# ADS1256.net
KiCad netlist of a schematic drawn in Altium Designer
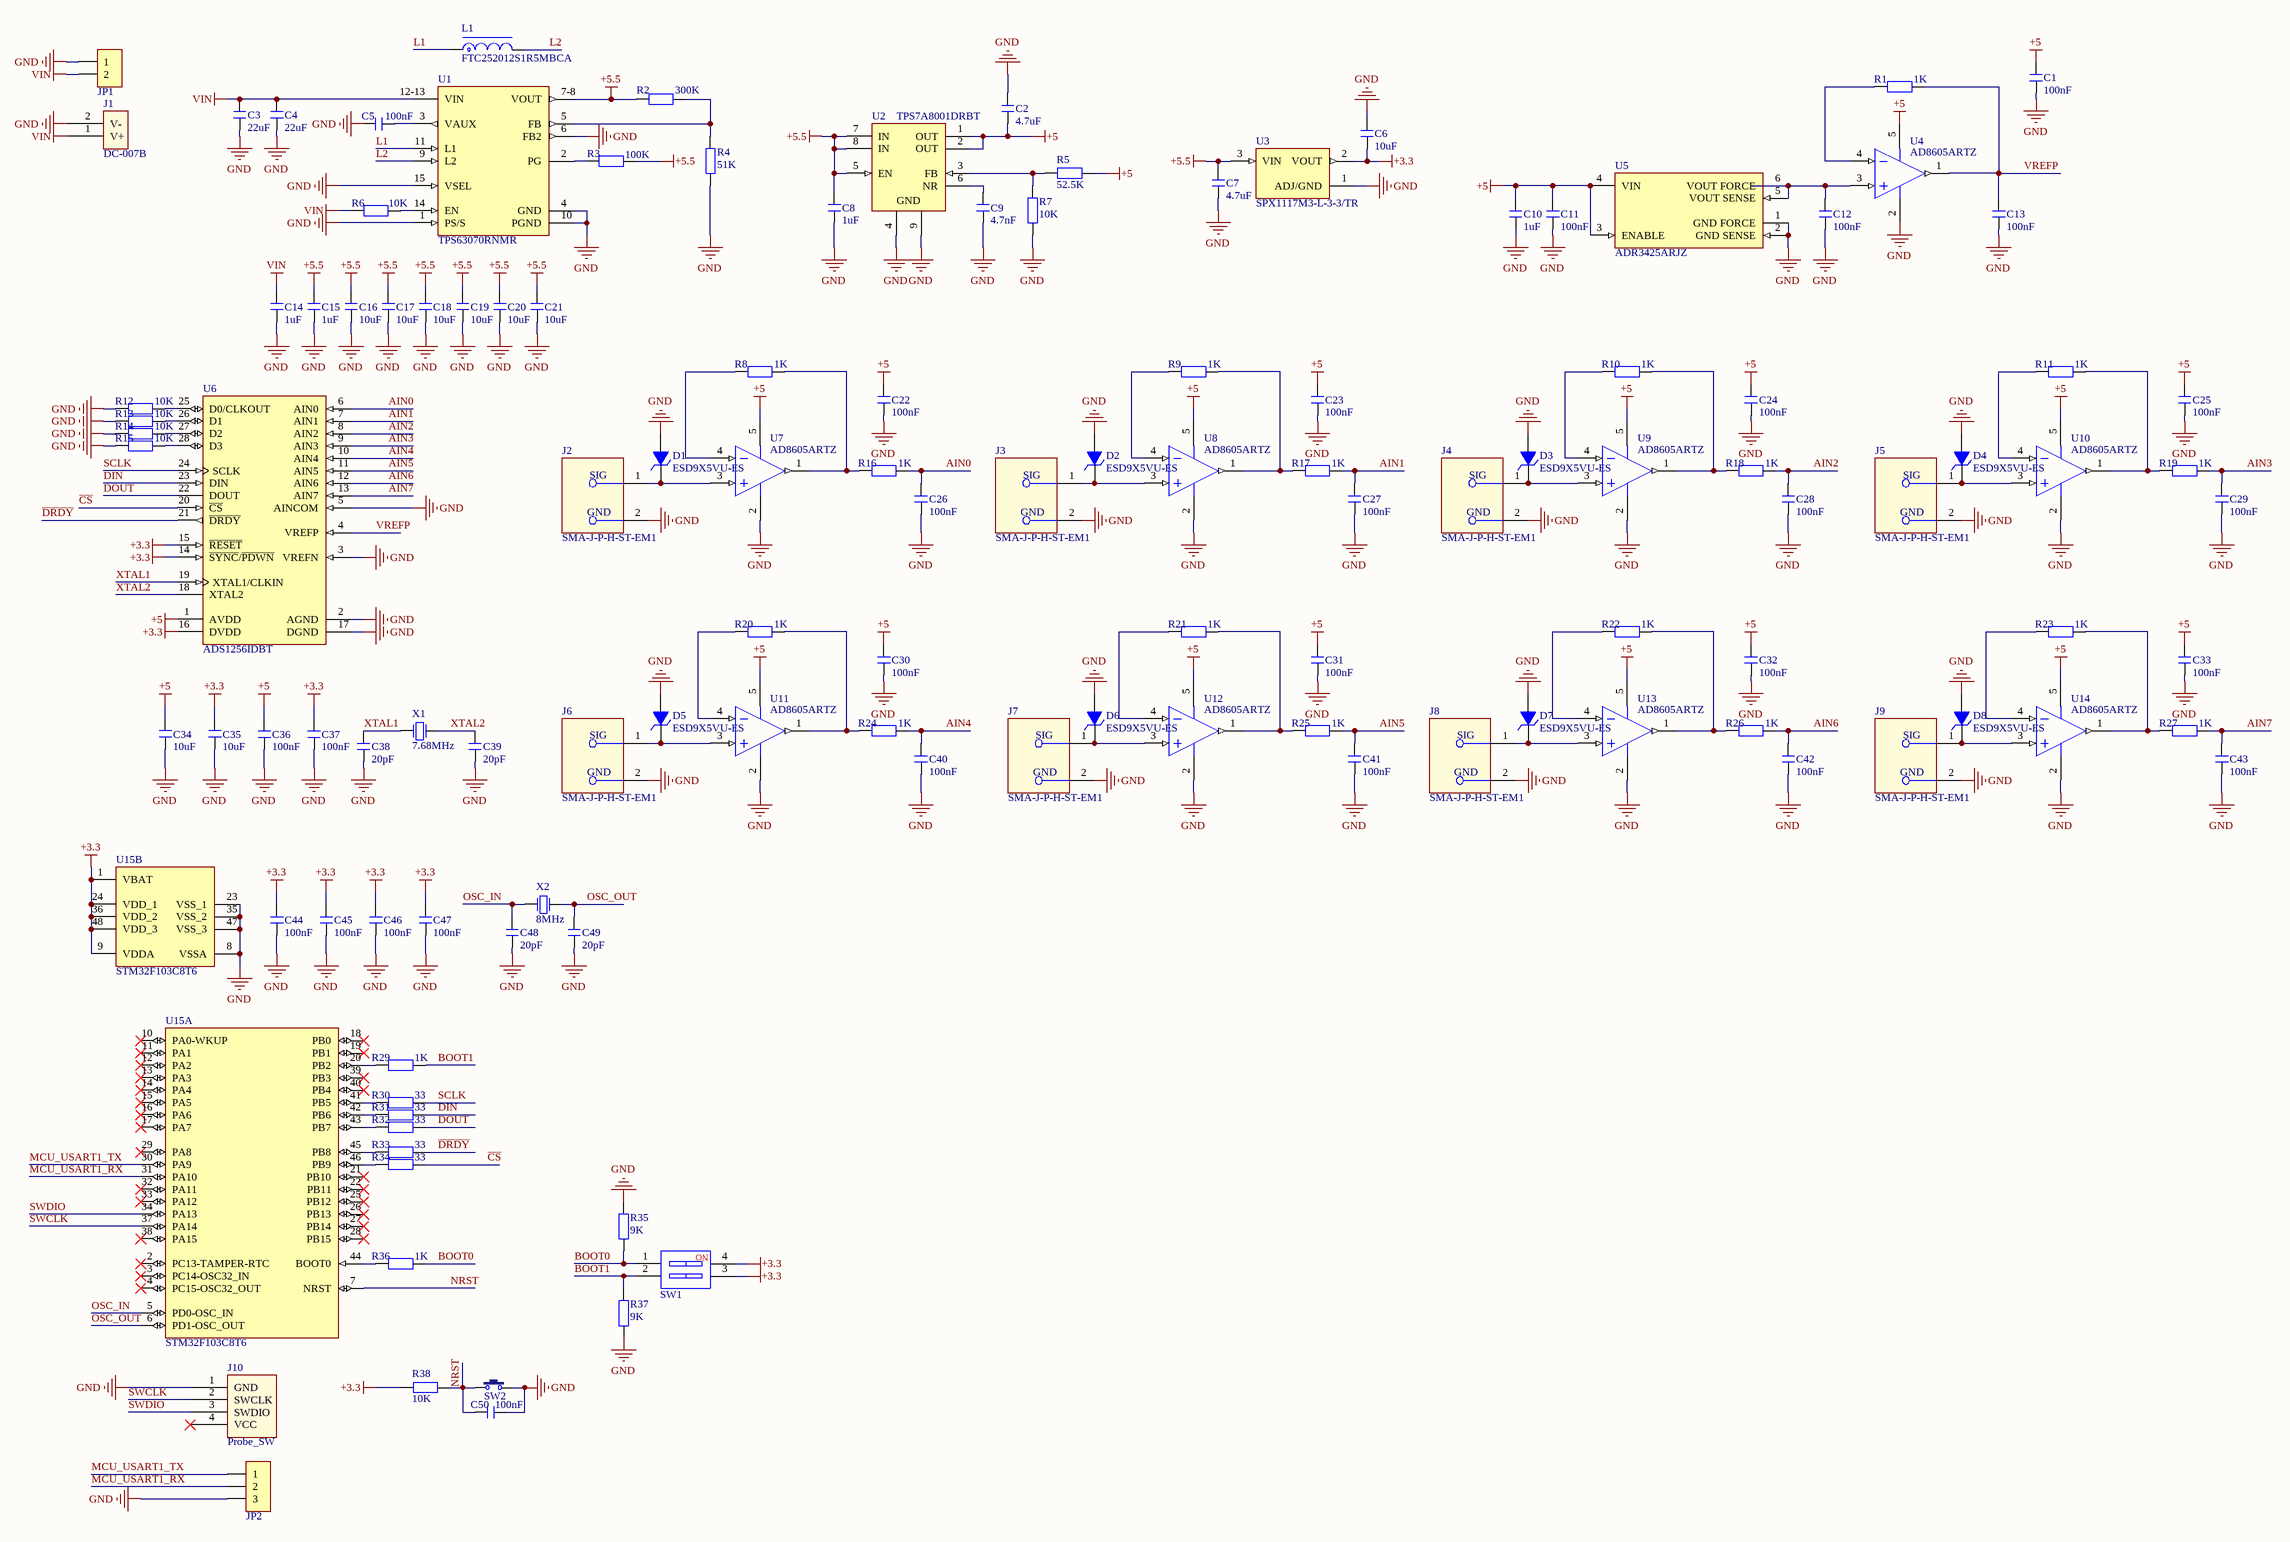
[diagram p0: ADS1256.SchDoc]

(export (version "E")
  (design (tool "Eeschema 10.0.6"))
  (components
    (comp (ref "C1")
      (value "100nF")
      (footprint "04 - 电容:C 0402_L")
      (description "贴片电容")
      (libsource (lib "01 - 电容-电阻-电感") (part "C"))
    )
    (comp (ref "C2")
      (value "4.7uF")
      (footprint "04 - 电容:C 0603_L")
      (description "贴片电容")
      (libsource (lib "01 - 电容-电阻-电感") (part "C"))
    )
    (comp (ref "C3")
      (value "22uF")
      (footprint "04 - 电容:C 1206_L")
      (description "贴片电容")
      (libsource (lib "01 - 电容-电阻-电感") (part "C"))
    )
    (comp (ref "C4")
      (value "22uF")
      (footprint "04 - 电容:C 1206_L")
      (description "贴片电容")
      (libsource (lib "01 - 电容-电阻-电感") (part "C"))
    )
    (comp (ref "C5")
      (value "100nF")
      (footprint "04 - 电容:C 0402_L")
      (description "贴片电容")
      (libsource (lib "01 - 电容-电阻-电感") (part "C"))
    )
    (comp (ref "C6")
      (value "10uF")
      (footprint "04 - 电容:C 0805_L")
      (description "贴片电容")
      (libsource (lib "01 - 电容-电阻-电感") (part "C"))
    )
    (comp (ref "C7")
      (value "4.7uF")
      (footprint "04 - 电容:C 0603_L")
      (description "贴片电容")
      (libsource (lib "01 - 电容-电阻-电感") (part "C"))
    )
    (comp (ref "C8")
      (value "1uF")
      (footprint "04 - 电容:C 0402_L")
      (description "贴片电容")
      (libsource (lib "01 - 电容-电阻-电感") (part "C"))
    )
    (comp (ref "C9")
      (value "4.7nF")
      (footprint "04 - 电容:C 0402_L")
      (description "贴片电容")
      (libsource (lib "01 - 电容-电阻-电感") (part "C"))
    )
    (comp (ref "C10")
      (value "1uF")
      (footprint "04 - 电容:C 0603_L")
      (description "贴片电容")
      (libsource (lib "01 - 电容-电阻-电感") (part "C"))
    )
    (comp (ref "C11")
      (value "100nF")
      (footprint "04 - 电容:C 0402_L")
      (description "贴片电容")
      (libsource (lib "01 - 电容-电阻-电感") (part "C"))
    )
    (comp (ref "C12")
      (value "100nF")
      (footprint "04 - 电容:C 0402_L")
      (description "贴片电容")
      (libsource (lib "01 - 电容-电阻-电感") (part "C"))
    )
    (comp (ref "C13")
      (value "100nF")
      (footprint "04 - 电容:C 0402_L")
      (description "贴片电容")
      (libsource (lib "01 - 电容-电阻-电感") (part "C"))
    )
    (comp (ref "C14")
      (value "1uF")
      (footprint "04 - 电容:C 0402_L")
      (description "贴片电容")
      (libsource (lib "01 - 电容-电阻-电感") (part "C"))
    )
    (comp (ref "C15")
      (value "1uF")
      (footprint "04 - 电容:C 0402_L")
      (description "贴片电容")
      (libsource (lib "01 - 电容-电阻-电感") (part "C"))
    )
    (comp (ref "C16")
      (value "10uF")
      (footprint "04 - 电容:C 0805_L")
      (description "贴片电容")
      (libsource (lib "01 - 电容-电阻-电感") (part "C"))
    )
    (comp (ref "C17")
      (value "10uF")
      (footprint "04 - 电容:C 0805_L")
      (description "贴片电容")
      (libsource (lib "01 - 电容-电阻-电感") (part "C"))
    )
    (comp (ref "C18")
      (value "10uF")
      (footprint "04 - 电容:C 0805_L")
      (description "贴片电容")
      (libsource (lib "01 - 电容-电阻-电感") (part "C"))
    )
    (comp (ref "C19")
      (value "10uF")
      (footprint "04 - 电容:C 0805_L")
      (description "贴片电容")
      (libsource (lib "01 - 电容-电阻-电感") (part "C"))
    )
    (comp (ref "C20")
      (value "10uF")
      (footprint "04 - 电容:C 0805_L")
      (description "贴片电容")
      (libsource (lib "01 - 电容-电阻-电感") (part "C"))
    )
    (comp (ref "C21")
      (value "10uF")
      (footprint "04 - 电容:C 0805_L")
      (description "贴片电容")
      (libsource (lib "01 - 电容-电阻-电感") (part "C"))
    )
    (comp (ref "C22")
      (value "100nF")
      (footprint "04 - 电容:C 0402_L")
      (description "贴片电容")
      (libsource (lib "01 - 电容-电阻-电感") (part "C"))
    )
    (comp (ref "C23")
      (value "100nF")
      (footprint "04 - 电容:C 0402_L")
      (description "贴片电容")
      (libsource (lib "01 - 电容-电阻-电感") (part "C"))
    )
    (comp (ref "C24")
      (value "100nF")
      (footprint "04 - 电容:C 0402_L")
      (description "贴片电容")
      (libsource (lib "01 - 电容-电阻-电感") (part "C"))
    )
    (comp (ref "C25")
      (value "100nF")
      (footprint "04 - 电容:C 0402_L")
      (description "贴片电容")
      (libsource (lib "01 - 电容-电阻-电感") (part "C"))
    )
    (comp (ref "C26")
      (value "100nF")
      (footprint "04 - 电容:C 0402_L")
      (description "贴片电容")
      (libsource (lib "01 - 电容-电阻-电感") (part "C"))
    )
    (comp (ref "C27")
      (value "100nF")
      (footprint "04 - 电容:C 0402_L")
      (description "贴片电容")
      (libsource (lib "01 - 电容-电阻-电感") (part "C"))
    )
    (comp (ref "C28")
      (value "100nF")
      (footprint "04 - 电容:C 0402_L")
      (description "贴片电容")
      (libsource (lib "01 - 电容-电阻-电感") (part "C"))
    )
    (comp (ref "C29")
      (value "100nF")
      (footprint "04 - 电容:C 0402_L")
      (description "贴片电容")
      (libsource (lib "01 - 电容-电阻-电感") (part "C"))
    )
    (comp (ref "C30")
      (value "100nF")
      (footprint "04 - 电容:C 0402_L")
      (description "贴片电容")
      (libsource (lib "01 - 电容-电阻-电感") (part "C"))
    )
    (comp (ref "C31")
      (value "100nF")
      (footprint "04 - 电容:C 0402_L")
      (description "贴片电容")
      (libsource (lib "01 - 电容-电阻-电感") (part "C"))
    )
    (comp (ref "C32")
      (value "100nF")
      (footprint "04 - 电容:C 0402_L")
      (description "贴片电容")
      (libsource (lib "01 - 电容-电阻-电感") (part "C"))
    )
    (comp (ref "C33")
      (value "100nF")
      (footprint "04 - 电容:C 0402_L")
      (description "贴片电容")
      (libsource (lib "01 - 电容-电阻-电感") (part "C"))
    )
    (comp (ref "C34")
      (value "10uF")
      (footprint "04 - 电容:C 0805_L")
      (description "贴片电容")
      (libsource (lib "01 - 电容-电阻-电感") (part "C"))
    )
    (comp (ref "C35")
      (value "10uF")
      (footprint "04 - 电容:C 0805_L")
      (description "贴片电容")
      (libsource (lib "01 - 电容-电阻-电感") (part "C"))
    )
    (comp (ref "C36")
      (value "100nF")
      (footprint "04 - 电容:C 0402_L")
      (description "贴片电容")
      (libsource (lib "01 - 电容-电阻-电感") (part "C"))
    )
    (comp (ref "C37")
      (value "100nF")
      (footprint "04 - 电容:C 0402_L")
      (description "贴片电容")
      (libsource (lib "01 - 电容-电阻-电感") (part "C"))
    )
    (comp (ref "C38")
      (value "20pF")
      (footprint "04 - 电容:C 0402_L")
      (description "贴片电容")
      (libsource (lib "01 - 电容-电阻-电感") (part "C"))
    )
    (comp (ref "C39")
      (value "20pF")
      (footprint "04 - 电容:C 0402_L")
      (description "贴片电容")
      (libsource (lib "01 - 电容-电阻-电感") (part "C"))
    )
    (comp (ref "C40")
      (value "100nF")
      (footprint "04 - 电容:C 0402_L")
      (description "贴片电容")
      (libsource (lib "01 - 电容-电阻-电感") (part "C"))
    )
    (comp (ref "C41")
      (value "100nF")
      (footprint "04 - 电容:C 0402_L")
      (description "贴片电容")
      (libsource (lib "01 - 电容-电阻-电感") (part "C"))
    )
    (comp (ref "C42")
      (value "100nF")
      (footprint "04 - 电容:C 0402_L")
      (description "贴片电容")
      (libsource (lib "01 - 电容-电阻-电感") (part "C"))
    )
    (comp (ref "C43")
      (value "100nF")
      (footprint "04 - 电容:C 0402_L")
      (description "贴片电容")
      (libsource (lib "01 - 电容-电阻-电感") (part "C"))
    )
    (comp (ref "C44")
      (value "100nF")
      (footprint "04 - 电容:C 0402_L")
      (description "贴片电容")
      (libsource (lib "01 - 电容-电阻-电感") (part "C"))
    )
    (comp (ref "C45")
      (value "100nF")
      (footprint "04 - 电容:C 0402_L")
      (description "贴片电容")
      (libsource (lib "01 - 电容-电阻-电感") (part "C"))
    )
    (comp (ref "C46")
      (value "100nF")
      (footprint "04 - 电容:C 0402_L")
      (description "贴片电容")
      (libsource (lib "01 - 电容-电阻-电感") (part "C"))
    )
    (comp (ref "C47")
      (value "100nF")
      (footprint "04 - 电容:C 0402_L")
      (description "贴片电容")
      (libsource (lib "01 - 电容-电阻-电感") (part "C"))
    )
    (comp (ref "C48")
      (value "20pF")
      (footprint "04 - 电容:C 0402_L")
      (description "贴片电容")
      (libsource (lib "01 - 电容-电阻-电感") (part "C"))
    )
    (comp (ref "C49")
      (value "20pF")
      (footprint "04 - 电容:C 0402_L")
      (description "贴片电容")
      (libsource (lib "01 - 电容-电阻-电感") (part "C"))
    )
    (comp (ref "C50")
      (value "100nF")
      (footprint "04 - 电容:C 0402_L")
      (description "贴片电容")
      (libsource (lib "01 - 电容-电阻-电感") (part "C"))
    )
    (comp (ref "D1")
      (value "ESD9X5VU-ES")
      (footprint "DFN1006-2")
      (description "ESD保护")
      (libsource (lib "02 - 二极管(LED)-三极管-整流桥") (part "ESD"))
    )
    (comp (ref "D2")
      (value "ESD9X5VU-ES")
      (footprint "DFN1006-2")
      (description "ESD保护")
      (libsource (lib "02 - 二极管(LED)-三极管-整流桥") (part "ESD"))
    )
    (comp (ref "D3")
      (value "ESD9X5VU-ES")
      (footprint "DFN1006-2")
      (description "ESD保护")
      (libsource (lib "02 - 二极管(LED)-三极管-整流桥") (part "ESD"))
    )
    (comp (ref "D4")
      (value "ESD9X5VU-ES")
      (footprint "DFN1006-2")
      (description "ESD保护")
      (libsource (lib "02 - 二极管(LED)-三极管-整流桥") (part "ESD"))
    )
    (comp (ref "D5")
      (value "ESD9X5VU-ES")
      (footprint "DFN1006-2")
      (description "ESD保护")
      (libsource (lib "02 - 二极管(LED)-三极管-整流桥") (part "ESD"))
    )
    (comp (ref "D6")
      (value "ESD9X5VU-ES")
      (footprint "DFN1006-2")
      (description "ESD保护")
      (libsource (lib "02 - 二极管(LED)-三极管-整流桥") (part "ESD"))
    )
    (comp (ref "D7")
      (value "ESD9X5VU-ES")
      (footprint "DFN1006-2")
      (description "ESD保护")
      (libsource (lib "02 - 二极管(LED)-三极管-整流桥") (part "ESD"))
    )
    (comp (ref "D8")
      (value "ESD9X5VU-ES")
      (footprint "DFN1006-2")
      (description "ESD保护")
      (libsource (lib "02 - 二极管(LED)-三极管-整流桥") (part "ESD"))
    )
    (comp (ref "J1") (value "DC-007B") (footprint "DC-007B") (libsource (lib "DC007B") (part "DC-007B")))
    (comp (ref "J2")
      (value "SMA-J-P-H-ST-EM1")
      (footprint "FP-SMA-J-P-H-ST-EM1-MFG")
      (description "CONN SMA JACK STR 50OHM EDGE MNT")
      (libsource (lib "卧式SMA") (part "CMP-02754-000006-1"))
    )
    (comp (ref "J3")
      (value "SMA-J-P-H-ST-EM1")
      (footprint "FP-SMA-J-P-H-ST-EM1-MFG")
      (description "CONN SMA JACK STR 50OHM EDGE MNT")
      (libsource (lib "卧式SMA") (part "CMP-02754-000006-1"))
    )
    (comp (ref "J4")
      (value "SMA-J-P-H-ST-EM1")
      (footprint "FP-SMA-J-P-H-ST-EM1-MFG")
      (description "CONN SMA JACK STR 50OHM EDGE MNT")
      (libsource (lib "卧式SMA") (part "CMP-02754-000006-1"))
    )
    (comp (ref "J5")
      (value "SMA-J-P-H-ST-EM1")
      (footprint "FP-SMA-J-P-H-ST-EM1-MFG")
      (description "CONN SMA JACK STR 50OHM EDGE MNT")
      (libsource (lib "卧式SMA") (part "CMP-02754-000006-1"))
    )
    (comp (ref "J6")
      (value "SMA-J-P-H-ST-EM1")
      (footprint "FP-SMA-J-P-H-ST-EM1-MFG")
      (description "CONN SMA JACK STR 50OHM EDGE MNT")
      (libsource (lib "卧式SMA") (part "CMP-02754-000006-1"))
    )
    (comp (ref "J7")
      (value "SMA-J-P-H-ST-EM1")
      (footprint "FP-SMA-J-P-H-ST-EM1-MFG")
      (description "CONN SMA JACK STR 50OHM EDGE MNT")
      (libsource (lib "卧式SMA") (part "CMP-02754-000006-1"))
    )
    (comp (ref "J8")
      (value "SMA-J-P-H-ST-EM1")
      (footprint "FP-SMA-J-P-H-ST-EM1-MFG")
      (description "CONN SMA JACK STR 50OHM EDGE MNT")
      (libsource (lib "卧式SMA") (part "CMP-02754-000006-1"))
    )
    (comp (ref "J9")
      (value "SMA-J-P-H-ST-EM1")
      (footprint "FP-SMA-J-P-H-ST-EM1-MFG")
      (description "CONN SMA JACK STR 50OHM EDGE MNT")
      (libsource (lib "卧式SMA") (part "CMP-02754-000006-1"))
    )
    (comp (ref "J10")
      (value "Probe_SW")
      (footprint "Probe_SW")
      (libsource (lib "Probe_SW") (part "Probe_SW"))
    )
    (comp (ref "JP1")
      (value "HDR-1X2")
      (footprint "68 - KF系列连接器:KF2510-LI-2P")
      (description "2P接插件")
      (libsource (lib "18 - 接插件-脚距2.54mm (100mil) ") (part "Header 2"))
    )
    (comp (ref "JP2")
      (value "HDR-1X3")
      (footprint "HDR2.54-LI-3P")
      (description "3P接插件")
      (libsource (lib "18 - 接插件-脚距2.54mm (100mil) ") (part "Header 3"))
    )
    (comp (ref "L1")
      (value "FTC252012S1R5MBCA")
      (footprint "NR2520")
      (description "功率屏蔽电感")
      (libsource (lib "01 - 电容-电阻-电感") (part "L-CDRH"))
    )
    (comp (ref "R1")
      (value "1K")
      (footprint "01 - 电阻:R 0402_L")
      (description "贴片电阻")
      (libsource (lib "01 - 电容-电阻-电感") (part "R"))
    )
    (comp (ref "R2")
      (value "300K")
      (footprint "01 - 电阻:R 0402_L")
      (description "贴片电阻")
      (libsource (lib "01 - 电容-电阻-电感") (part "R"))
    )
    (comp (ref "R3")
      (value "100K")
      (footprint "01 - 电阻:R 0402_L")
      (description "贴片电阻")
      (libsource (lib "01 - 电容-电阻-电感") (part "R"))
    )
    (comp (ref "R4")
      (value "51K")
      (footprint "01 - 电阻:R 0402_L")
      (description "贴片电阻")
      (libsource (lib "01 - 电容-电阻-电感") (part "R"))
    )
    (comp (ref "R5")
      (value "52.5K")
      (footprint "01 - 电阻:R 0402_L")
      (description "贴片电阻")
      (libsource (lib "01 - 电容-电阻-电感") (part "R"))
    )
    (comp (ref "R6")
      (value "10K")
      (footprint "01 - 电阻:R 0402_L")
      (description "贴片电阻")
      (libsource (lib "01 - 电容-电阻-电感") (part "R"))
    )
    (comp (ref "R7")
      (value "10K")
      (footprint "01 - 电阻:R 0402_L")
      (description "贴片电阻")
      (libsource (lib "01 - 电容-电阻-电感") (part "R"))
    )
    (comp (ref "R8")
      (value "1K")
      (footprint "01 - 电阻:R 0402_L")
      (description "贴片电阻")
      (libsource (lib "01 - 电容-电阻-电感") (part "R"))
    )
    (comp (ref "R9")
      (value "1K")
      (footprint "01 - 电阻:R 0402_L")
      (description "贴片电阻")
      (libsource (lib "01 - 电容-电阻-电感") (part "R"))
    )
    (comp (ref "R10")
      (value "1K")
      (footprint "01 - 电阻:R 0402_L")
      (description "贴片电阻")
      (libsource (lib "01 - 电容-电阻-电感") (part "R"))
    )
    (comp (ref "R11")
      (value "1K")
      (footprint "01 - 电阻:R 0402_L")
      (description "贴片电阻")
      (libsource (lib "01 - 电容-电阻-电感") (part "R"))
    )
    (comp (ref "R12")
      (value "10K")
      (footprint "01 - 电阻:R 0402_L")
      (description "贴片电阻")
      (libsource (lib "01 - 电容-电阻-电感") (part "R"))
    )
    (comp (ref "R13")
      (value "10K")
      (footprint "01 - 电阻:R 0402_L")
      (description "贴片电阻")
      (libsource (lib "01 - 电容-电阻-电感") (part "R"))
    )
    (comp (ref "R14")
      (value "10K")
      (footprint "01 - 电阻:R 0402_L")
      (description "贴片电阻")
      (libsource (lib "01 - 电容-电阻-电感") (part "R"))
    )
    (comp (ref "R15")
      (value "10K")
      (footprint "01 - 电阻:R 0402_L")
      (description "贴片电阻")
      (libsource (lib "01 - 电容-电阻-电感") (part "R"))
    )
    (comp (ref "R16")
      (value "1K")
      (footprint "01 - 电阻:R 0402_L")
      (description "贴片电阻")
      (libsource (lib "01 - 电容-电阻-电感") (part "R"))
    )
    (comp (ref "R17")
      (value "1K")
      (footprint "01 - 电阻:R 0402_L")
      (description "贴片电阻")
      (libsource (lib "01 - 电容-电阻-电感") (part "R"))
    )
    (comp (ref "R18")
      (value "1K")
      (footprint "01 - 电阻:R 0402_L")
      (description "贴片电阻")
      (libsource (lib "01 - 电容-电阻-电感") (part "R"))
    )
    (comp (ref "R19")
      (value "1K")
      (footprint "01 - 电阻:R 0402_L")
      (description "贴片电阻")
      (libsource (lib "01 - 电容-电阻-电感") (part "R"))
    )
    (comp (ref "R20")
      (value "1K")
      (footprint "01 - 电阻:R 0402_L")
      (description "贴片电阻")
      (libsource (lib "01 - 电容-电阻-电感") (part "R"))
    )
    (comp (ref "R21")
      (value "1K")
      (footprint "01 - 电阻:R 0402_L")
      (description "贴片电阻")
      (libsource (lib "01 - 电容-电阻-电感") (part "R"))
    )
    (comp (ref "R22")
      (value "1K")
      (footprint "01 - 电阻:R 0402_L")
      (description "贴片电阻")
      (libsource (lib "01 - 电容-电阻-电感") (part "R"))
    )
    (comp (ref "R23")
      (value "1K")
      (footprint "01 - 电阻:R 0402_L")
      (description "贴片电阻")
      (libsource (lib "01 - 电容-电阻-电感") (part "R"))
    )
    (comp (ref "R24")
      (value "1K")
      (footprint "01 - 电阻:R 0402_L")
      (description "贴片电阻")
      (libsource (lib "01 - 电容-电阻-电感") (part "R"))
    )
    (comp (ref "R25")
      (value "1K")
      (footprint "01 - 电阻:R 0402_L")
      (description "贴片电阻")
      (libsource (lib "01 - 电容-电阻-电感") (part "R"))
    )
    (comp (ref "R26")
      (value "1K")
      (footprint "01 - 电阻:R 0402_L")
      (description "贴片电阻")
      (libsource (lib "01 - 电容-电阻-电感") (part "R"))
    )
    (comp (ref "R27")
      (value "1K")
      (footprint "01 - 电阻:R 0402_L")
      (description "贴片电阻")
      (libsource (lib "01 - 电容-电阻-电感") (part "R"))
    )
    (comp (ref "R29")
      (value "1K")
      (footprint "01 - 电阻:R 0402_L")
      (description "贴片电阻")
      (libsource (lib "01 - 电容-电阻-电感") (part "R"))
    )
    (comp (ref "R30")
      (value "33")
      (footprint "01 - 电阻:R 0402_L")
      (description "贴片电阻")
      (libsource (lib "01 - 电容-电阻-电感") (part "R"))
    )
    (comp (ref "R31")
      (value "33")
      (footprint "01 - 电阻:R 0402_L")
      (description "贴片电阻")
      (libsource (lib "01 - 电容-电阻-电感") (part "R"))
    )
    (comp (ref "R32")
      (value "33")
      (footprint "01 - 电阻:R 0402_L")
      (description "贴片电阻")
      (libsource (lib "01 - 电容-电阻-电感") (part "R"))
    )
    (comp (ref "R33")
      (value "33")
      (footprint "01 - 电阻:R 0402_L")
      (description "贴片电阻")
      (libsource (lib "01 - 电容-电阻-电感") (part "R"))
    )
    (comp (ref "R34")
      (value "33")
      (footprint "01 - 电阻:R 0402_L")
      (description "贴片电阻")
      (libsource (lib "01 - 电容-电阻-电感") (part "R"))
    )
    (comp (ref "R35")
      (value "9K")
      (footprint "01 - 电阻:R 0402_L")
      (description "贴片电阻")
      (libsource (lib "01 - 电容-电阻-电感") (part "R"))
    )
    (comp (ref "R36")
      (value "1K")
      (footprint "01 - 电阻:R 0402_L")
      (description "贴片电阻")
      (libsource (lib "01 - 电容-电阻-电感") (part "R"))
    )
    (comp (ref "R37")
      (value "9K")
      (footprint "01 - 电阻:R 0402_L")
      (description "贴片电阻")
      (libsource (lib "01 - 电容-电阻-电感") (part "R"))
    )
    (comp (ref "R38")
      (value "10K")
      (footprint "01 - 电阻:R 0402_L")
      (description "贴片电阻")
      (libsource (lib "01 - 电容-电阻-电感") (part "R"))
    )
    (comp (ref "SW1")
      (value "SW-2P")
      (footprint "CSW1.27 SMD-2P")
      (description "2路编码开关")
      (libsource (lib "03 - 按键-开关-晶振-蜂鸣器") (part "SW-2P"))
    )
    (comp (ref "SW2")
      (value "3x6x5")
      (footprint "TSW SMD-3*6*2.5")
      (description "3x6轻触开关")
      (libsource (lib "03 - 按键-开关-晶振-蜂鸣器") (part "TSW 3x6"))
    )
    (comp (ref "U1")
      (value "TPS63070RNMR")
      (footprint "FP-RNM0015A-MFG")
      (description "IC REG BCK BST ADJ 3.6A 15VQFN")
      (libsource (lib "TPS63070") (part "CMP-04918-000409-1"))
    )
    (comp (ref "U2")
      (value "TPS7A8001DRBT")
      (footprint "TPS7A8001DRBT:DRB0008A_V")
      (fields (field (name "MANUFACTURER") "Texas Instruments"))
      (libsource (lib "TPS7A8001DRBT") (part "CMP-0395-00597-2"))
    )
    (comp (ref "U3")
      (value "SPX1117M3-L-3-3/TR")
      (footprint "SPX1117M3-L-3-3_TR:SOT230P700X180-3N")
      (description "Linear Voltage Regulator IC Positive Fixed 1 Output 800mA SOT-223")
      (fields (field (name "MF") "MaxLinear, Inc."))
      (libsource (lib "SPX1117M3-L-3-3_TR") (part "SPX1117M3-L-3-3/TR"))
    )
    (comp (ref "U4")
      (value "AD8605ARTZ")
      (footprint "17 - SOT封装:SOT23-5")
      (description "Precision Low Noise CMOS Rail-to-Rail Input/Output Operational Amplifiers")
      (libsource (lib "OPAMP") (part "AD8605ARTZ"))
    )
    (comp (ref "U5")
      (value "ADR3425ARJZ")
      (footprint "SOT23-6L")
      (description "Micropower, High Accuracy\r\nVoltage References, 2.5V")
      (fields (field (name "TOLERANCE") "0.1%"))
      (libsource (lib "ADR3435ARJZ") (part "ADR3425ARJZ"))
    )
    (comp (ref "U6")
      (value "ADS1256IDBT")
      (footprint "12 - SSOP封装:SSOP28")
      (fields (field (name "MANUFACTURER") "Texas Instruments"))
      (libsource (lib "ADS1256IDBT") (part "ADS1256IDBT"))
    )
    (comp (ref "U7")
      (value "AD8605ARTZ")
      (footprint "17 - SOT封装:SOT23-5")
      (description "Precision Low Noise CMOS Rail-to-Rail Input/Output Operational Amplifiers")
      (libsource (lib "OPAMP") (part "AD8605ARTZ"))
    )
    (comp (ref "U8")
      (value "AD8605ARTZ")
      (footprint "17 - SOT封装:SOT23-5")
      (description "Precision Low Noise CMOS Rail-to-Rail Input/Output Operational Amplifiers")
      (libsource (lib "OPAMP") (part "AD8605ARTZ"))
    )
    (comp (ref "U9")
      (value "AD8605ARTZ")
      (footprint "17 - SOT封装:SOT23-5")
      (description "Precision Low Noise CMOS Rail-to-Rail Input/Output Operational Amplifiers")
      (libsource (lib "OPAMP") (part "AD8605ARTZ"))
    )
    (comp (ref "U10")
      (value "AD8605ARTZ")
      (footprint "17 - SOT封装:SOT23-5")
      (description "Precision Low Noise CMOS Rail-to-Rail Input/Output Operational Amplifiers")
      (libsource (lib "OPAMP") (part "AD8605ARTZ"))
    )
    (comp (ref "U11")
      (value "AD8605ARTZ")
      (footprint "17 - SOT封装:SOT23-5")
      (description "Precision Low Noise CMOS Rail-to-Rail Input/Output Operational Amplifiers")
      (libsource (lib "OPAMP") (part "AD8605ARTZ"))
    )
    (comp (ref "U12")
      (value "AD8605ARTZ")
      (footprint "17 - SOT封装:SOT23-5")
      (description "Precision Low Noise CMOS Rail-to-Rail Input/Output Operational Amplifiers")
      (libsource (lib "OPAMP") (part "AD8605ARTZ"))
    )
    (comp (ref "U13")
      (value "AD8605ARTZ")
      (footprint "17 - SOT封装:SOT23-5")
      (description "Precision Low Noise CMOS Rail-to-Rail Input/Output Operational Amplifiers")
      (libsource (lib "OPAMP") (part "AD8605ARTZ"))
    )
    (comp (ref "U14")
      (value "AD8605ARTZ")
      (footprint "17 - SOT封装:SOT23-5")
      (description "Precision Low Noise CMOS Rail-to-Rail Input/Output Operational Amplifiers")
      (libsource (lib "OPAMP") (part "AD8605ARTZ"))
    )
    (comp (ref "U15")
      (value "STM32F103C8T6")
      (footprint "STM-LQFP48_L")
      (libsource (lib "STM32F103C8T6") (part "CMP-0237-00215-3"))
    )
    (comp (ref "X1")
      (value "7.68MHz")
      (footprint "09 - 晶振-晶体:OSC HC-49SMD")
      (description "2脚无源脚晶振")
      (libsource (lib "03 - 按键-开关-晶振-蜂鸣器") (part "XTAL-2P"))
    )
    (comp (ref "X2")
      (value "8MHz")
      (footprint "OSC 5032-2P")
      (description "2脚无源脚晶振")
      (libsource (lib "03 - 按键-开关-晶振-蜂鸣器") (part "XTAL-2P"))
    )
  )
  (nets
    (net (code "1") (name "+3.3") (class "Default")
      (node (ref "C35") (pin "1") (pinfunction "1_1") (pintype "passive"))
      (node (ref "C37") (pin "2") (pinfunction "2_2") (pintype "passive"))
      (node (ref "C44") (pin "2") (pinfunction "2_2") (pintype "passive"))
      (node (ref "C45") (pin "2") (pinfunction "2_2") (pintype "passive"))
      (node (ref "C46") (pin "2") (pinfunction "2_2") (pintype "passive"))
      (node (ref "C47") (pin "2") (pinfunction "2_2") (pintype "passive"))
      (node (ref "C6") (pin "1") (pinfunction "1_1") (pintype "passive"))
      (node (ref "R38") (pin "2") (pinfunction "2_2") (pintype "passive"))
      (node (ref "SW1") (pin "3") (pinfunction "3_3") (pintype "passive"))
      (node (ref "SW1") (pin "4") (pinfunction "4_4") (pintype "passive"))
      (node (ref "U15") (pin "1") (pinfunction "VBAT_1") (pintype "power_in"))
      (node (ref "U15") (pin "24") (pinfunction "VDD_1_24") (pintype "power_in"))
      (node (ref "U15") (pin "36") (pinfunction "VDD_2_36") (pintype "power_in"))
      (node (ref "U15") (pin "48") (pinfunction "VDD_3_48") (pintype "power_in"))
      (node (ref "U15") (pin "9") (pinfunction "VDDA_9") (pintype "power_in"))
      (node (ref "U3") (pin "2") (pinfunction "VOUT_2") (pintype "output"))
      (node (ref "U6") (pin "14") (pinfunction "~{SYNC}/~{PDWN}_14") (pintype "input"))
      (node (ref "U6") (pin "15") (pinfunction "~{RESET}_15") (pintype "input"))
      (node (ref "U6") (pin "16") (pinfunction "DVDD_16") (pintype "power_in"))
    )
    (net (code "2") (name "+5") (class "Default")
      (node (ref "C1") (pin "2") (pinfunction "2_2") (pintype "passive"))
      (node (ref "C10") (pin "2") (pinfunction "2_2") (pintype "passive"))
      (node (ref "C11") (pin "2") (pinfunction "2_2") (pintype "passive"))
      (node (ref "C2") (pin "1") (pinfunction "1_1") (pintype "passive"))
      (node (ref "C22") (pin "2") (pinfunction "2_2") (pintype "passive"))
      (node (ref "C23") (pin "2") (pinfunction "2_2") (pintype "passive"))
      (node (ref "C24") (pin "2") (pinfunction "2_2") (pintype "passive"))
      (node (ref "C25") (pin "2") (pinfunction "2_2") (pintype "passive"))
      (node (ref "C30") (pin "2") (pinfunction "2_2") (pintype "passive"))
      (node (ref "C31") (pin "2") (pinfunction "2_2") (pintype "passive"))
      (node (ref "C32") (pin "2") (pinfunction "2_2") (pintype "passive"))
      (node (ref "C33") (pin "2") (pinfunction "2_2") (pintype "passive"))
      (node (ref "C34") (pin "1") (pinfunction "1_1") (pintype "passive"))
      (node (ref "C36") (pin "2") (pinfunction "2_2") (pintype "passive"))
      (node (ref "R5") (pin "1") (pinfunction "1_1") (pintype "passive"))
      (node (ref "U10") (pin "5") (pinfunction "+V_5") (pintype "power_in"))
      (node (ref "U11") (pin "5") (pinfunction "+V_5") (pintype "power_in"))
      (node (ref "U12") (pin "5") (pinfunction "+V_5") (pintype "power_in"))
      (node (ref "U13") (pin "5") (pinfunction "+V_5") (pintype "power_in"))
      (node (ref "U14") (pin "5") (pinfunction "+V_5") (pintype "power_in"))
      (node (ref "U2") (pin "1") (pinfunction "OUT_1") (pintype "power_in"))
      (node (ref "U2") (pin "2") (pinfunction "OUT_2") (pintype "power_in"))
      (node (ref "U4") (pin "5") (pinfunction "+V_5") (pintype "power_in"))
      (node (ref "U5") (pin "3") (pinfunction "ENABLE_3") (pintype "input"))
      (node (ref "U5") (pin "4") (pinfunction "VIN_4") (pintype "power_in"))
      (node (ref "U6") (pin "1") (pinfunction "AVDD_1") (pintype "power_in"))
      (node (ref "U7") (pin "5") (pinfunction "+V_5") (pintype "power_in"))
      (node (ref "U8") (pin "5") (pinfunction "+V_5") (pintype "power_in"))
      (node (ref "U9") (pin "5") (pinfunction "+V_5") (pintype "power_in"))
    )
    (net (code "3") (name "+5.5") (class "Default")
      (node (ref "C15") (pin "1") (pinfunction "1_1") (pintype "passive"))
      (node (ref "C16") (pin "1") (pinfunction "1_1") (pintype "passive"))
      (node (ref "C17") (pin "1") (pinfunction "1_1") (pintype "passive"))
      (node (ref "C18") (pin "1") (pinfunction "1_1") (pintype "passive"))
      (node (ref "C19") (pin "1") (pinfunction "1_1") (pintype "passive"))
      (node (ref "C20") (pin "1") (pinfunction "1_1") (pintype "passive"))
      (node (ref "C21") (pin "1") (pinfunction "1_1") (pintype "passive"))
      (node (ref "C7") (pin "2") (pinfunction "2_2") (pintype "passive"))
      (node (ref "C8") (pin "2") (pinfunction "2_2") (pintype "passive"))
      (node (ref "R2") (pin "2") (pinfunction "2_2") (pintype "passive"))
      (node (ref "R3") (pin "1") (pinfunction "1_1") (pintype "passive"))
      (node (ref "U1") (pin "7-8") (pinfunction "VOUT_7-8") (pintype "output"))
      (node (ref "U2") (pin "5") (pinfunction "EN_5") (pintype "input"))
      (node (ref "U2") (pin "7") (pinfunction "IN_7") (pintype "power_in"))
      (node (ref "U2") (pin "8") (pinfunction "IN_8") (pintype "power_in"))
      (node (ref "U3") (pin "3") (pinfunction "VIN_3") (pintype "input"))
    )
    (net (code "4") (name "/AIN0") (class "Default")
      (node (ref "C26") (pin "2") (pinfunction "2_2") (pintype "passive"))
      (node (ref "R16") (pin "2") (pinfunction "2_2") (pintype "passive"))
      (node (ref "U6") (pin "6") (pinfunction "AIN0_6") (pintype "input"))
    )
    (net (code "5") (name "/AIN1") (class "Default")
      (node (ref "C27") (pin "2") (pinfunction "2_2") (pintype "passive"))
      (node (ref "R17") (pin "2") (pinfunction "2_2") (pintype "passive"))
      (node (ref "U6") (pin "7") (pinfunction "AIN1_7") (pintype "input"))
    )
    (net (code "6") (name "/AIN2") (class "Default")
      (node (ref "C28") (pin "2") (pinfunction "2_2") (pintype "passive"))
      (node (ref "R18") (pin "2") (pinfunction "2_2") (pintype "passive"))
      (node (ref "U6") (pin "8") (pinfunction "AIN2_8") (pintype "input"))
    )
    (net (code "7") (name "/AIN3") (class "Default")
      (node (ref "C29") (pin "2") (pinfunction "2_2") (pintype "passive"))
      (node (ref "R19") (pin "2") (pinfunction "2_2") (pintype "passive"))
      (node (ref "U6") (pin "9") (pinfunction "AIN3_9") (pintype "input"))
    )
    (net (code "8") (name "/AIN4") (class "Default")
      (node (ref "C40") (pin "2") (pinfunction "2_2") (pintype "passive"))
      (node (ref "R24") (pin "2") (pinfunction "2_2") (pintype "passive"))
      (node (ref "U6") (pin "10") (pinfunction "AIN4_10") (pintype "input"))
    )
    (net (code "9") (name "/AIN5") (class "Default")
      (node (ref "C41") (pin "2") (pinfunction "2_2") (pintype "passive"))
      (node (ref "R25") (pin "2") (pinfunction "2_2") (pintype "passive"))
      (node (ref "U6") (pin "11") (pinfunction "AIN5_11") (pintype "input"))
    )
    (net (code "10") (name "/AIN6") (class "Default")
      (node (ref "C42") (pin "2") (pinfunction "2_2") (pintype "passive"))
      (node (ref "R26") (pin "2") (pinfunction "2_2") (pintype "passive"))
      (node (ref "U6") (pin "12") (pinfunction "AIN6_12") (pintype "input"))
    )
    (net (code "11") (name "/AIN7") (class "Default")
      (node (ref "C43") (pin "2") (pinfunction "2_2") (pintype "passive"))
      (node (ref "R27") (pin "2") (pinfunction "2_2") (pintype "passive"))
      (node (ref "U6") (pin "13") (pinfunction "AIN7_13") (pintype "input"))
    )
    (net (code "12") (name "/BOOT0") (class "Default")
      (node (ref "R35") (pin "1") (pinfunction "1_1") (pintype "passive"))
      (node (ref "R36") (pin "2") (pinfunction "2_2") (pintype "passive"))
      (node (ref "SW1") (pin "1") (pinfunction "1_1") (pintype "passive"))
    )
    (net (code "13") (name "/BOOT1") (class "Default")
      (node (ref "R29") (pin "2") (pinfunction "2_2") (pintype "passive"))
      (node (ref "R37") (pin "2") (pinfunction "2_2") (pintype "passive"))
      (node (ref "SW1") (pin "2") (pinfunction "2_2") (pintype "passive"))
    )
    (net (code "14") (name "/DIN") (class "Default")
      (node (ref "R31") (pin "2") (pinfunction "2_2") (pintype "passive"))
      (node (ref "U6") (pin "23") (pinfunction "DIN_23") (pintype "input"))
    )
    (net (code "15") (name "/DOUT") (class "Default")
      (node (ref "R32") (pin "2") (pinfunction "2_2") (pintype "passive"))
      (node (ref "U6") (pin "22") (pinfunction "DOUT_22") (pintype "tri_state"))
    )
    (net (code "16") (name "/L1") (class "Default")
      (node (ref "L1") (pin "1") (pinfunction "1_1") (pintype "passive"))
      (node (ref "U1") (pin "11") (pinfunction "L1_11") (pintype "input"))
    )
    (net (code "17") (name "/L2") (class "Default")
      (node (ref "L1") (pin "2") (pinfunction "2_2") (pintype "passive"))
      (node (ref "U1") (pin "9") (pinfunction "L2_9") (pintype "input"))
    )
    (net (code "18") (name "/MCU_USART1_RX") (class "Default")
      (node (ref "JP2") (pin "2") (pinfunction "2_2") (pintype "passive"))
      (node (ref "U15") (pin "31") (pinfunction "PA10_31") (pintype "bidirectional"))
    )
    (net (code "19") (name "/MCU_USART1_TX") (class "Default")
      (node (ref "JP2") (pin "1") (pinfunction "1_1") (pintype "passive"))
      (node (ref "U15") (pin "30") (pinfunction "PA9_30") (pintype "bidirectional"))
    )
    (net (code "20") (name "/NRST") (class "Default")
      (node (ref "C50") (pin "1") (pinfunction "1_1") (pintype "passive"))
      (node (ref "R38") (pin "1") (pinfunction "1_1") (pintype "passive"))
      (node (ref "SW2") (pin "1") (pinfunction "1_1") (pintype "passive"))
      (node (ref "U15") (pin "7") (pinfunction "NRST_7") (pintype "bidirectional"))
    )
    (net (code "21") (name "/OSC_IN") (class "Default")
      (node (ref "C48") (pin "2") (pinfunction "2_2") (pintype "passive"))
      (node (ref "U15") (pin "5") (pinfunction "PD0-OSC_IN_5") (pintype "bidirectional"))
      (node (ref "X2") (pin "1") (pinfunction "1_1") (pintype "passive"))
    )
    (net (code "22") (name "/OSC_OUT") (class "Default")
      (node (ref "C49") (pin "2") (pinfunction "2_2") (pintype "passive"))
      (node (ref "U15") (pin "6") (pinfunction "PD1-OSC_OUT_6") (pintype "bidirectional"))
      (node (ref "X2") (pin "2") (pinfunction "2_2") (pintype "passive"))
    )
    (net (code "23") (name "/SCLK") (class "Default")
      (node (ref "R30") (pin "2") (pinfunction "2_2") (pintype "passive"))
      (node (ref "U6") (pin "24") (pinfunction "SCLK_24") (pintype "input"))
    )
    (net (code "24") (name "/SWCLK") (class "Default")
      (node (ref "J10") (pin "2") (pinfunction "SWCLK_2") (pintype "passive"))
      (node (ref "U15") (pin "37") (pinfunction "PA14_37") (pintype "bidirectional"))
    )
    (net (code "25") (name "/SWDIO") (class "Default")
      (node (ref "J10") (pin "3") (pinfunction "SWDIO_3") (pintype "passive"))
      (node (ref "U15") (pin "34") (pinfunction "PA13_34") (pintype "bidirectional"))
    )
    (net (code "26") (name "/VREFP") (class "Default")
      (node (ref "C13") (pin "2") (pinfunction "2_2") (pintype "passive"))
      (node (ref "R1") (pin "2") (pinfunction "2_2") (pintype "passive"))
      (node (ref "U4") (pin "1") (pinfunction "OUT_1") (pintype "output"))
      (node (ref "U6") (pin "4") (pinfunction "VREFP_4") (pintype "input"))
    )
    (net (code "27") (name "/XTAL1") (class "Default")
      (node (ref "C38") (pin "2") (pinfunction "2_2") (pintype "passive"))
      (node (ref "U6") (pin "19") (pinfunction "XTAL1/CLKIN_19") (pintype "input"))
      (node (ref "X1") (pin "1") (pinfunction "1_1") (pintype "passive"))
    )
    (net (code "28") (name "/XTAL2") (class "Default")
      (node (ref "C39") (pin "2") (pinfunction "2_2") (pintype "passive"))
      (node (ref "U6") (pin "18") (pinfunction "XTAL2_18") (pintype "passive"))
      (node (ref "X1") (pin "2") (pinfunction "2_2") (pintype "passive"))
    )
    (net (code "29") (name "/~{CS}") (class "Default")
      (node (ref "R34") (pin "2") (pinfunction "2_2") (pintype "passive"))
      (node (ref "U6") (pin "20") (pinfunction "~{CS}_20") (pintype "input"))
    )
    (net (code "30") (name "/~{DRDY}") (class "Default")
      (node (ref "R33") (pin "2") (pinfunction "2_2") (pintype "passive"))
      (node (ref "U6") (pin "21") (pinfunction "~{DRDY}_21") (pintype "output"))
    )
    (net (code "31") (name "GND") (class "Default")
      (node (ref "C1") (pin "1") (pinfunction "1_1") (pintype "passive"))
      (node (ref "C10") (pin "1") (pinfunction "1_1") (pintype "passive"))
      (node (ref "C11") (pin "1") (pinfunction "1_1") (pintype "passive"))
      (node (ref "C12") (pin "1") (pinfunction "1_1") (pintype "passive"))
      (node (ref "C13") (pin "1") (pinfunction "1_1") (pintype "passive"))
      (node (ref "C14") (pin "2") (pinfunction "2_2") (pintype "passive"))
      (node (ref "C15") (pin "2") (pinfunction "2_2") (pintype "passive"))
      (node (ref "C16") (pin "2") (pinfunction "2_2") (pintype "passive"))
      (node (ref "C17") (pin "2") (pinfunction "2_2") (pintype "passive"))
      (node (ref "C18") (pin "2") (pinfunction "2_2") (pintype "passive"))
      (node (ref "C19") (pin "2") (pinfunction "2_2") (pintype "passive"))
      (node (ref "C2") (pin "2") (pinfunction "2_2") (pintype "passive"))
      (node (ref "C20") (pin "2") (pinfunction "2_2") (pintype "passive"))
      (node (ref "C21") (pin "2") (pinfunction "2_2") (pintype "passive"))
      (node (ref "C22") (pin "1") (pinfunction "1_1") (pintype "passive"))
      (node (ref "C23") (pin "1") (pinfunction "1_1") (pintype "passive"))
      (node (ref "C24") (pin "1") (pinfunction "1_1") (pintype "passive"))
      (node (ref "C25") (pin "1") (pinfunction "1_1") (pintype "passive"))
      (node (ref "C26") (pin "1") (pinfunction "1_1") (pintype "passive"))
      (node (ref "C27") (pin "1") (pinfunction "1_1") (pintype "passive"))
      (node (ref "C28") (pin "1") (pinfunction "1_1") (pintype "passive"))
      (node (ref "C29") (pin "1") (pinfunction "1_1") (pintype "passive"))
      (node (ref "C3") (pin "1") (pinfunction "1_1") (pintype "passive"))
      (node (ref "C30") (pin "1") (pinfunction "1_1") (pintype "passive"))
      (node (ref "C31") (pin "1") (pinfunction "1_1") (pintype "passive"))
      (node (ref "C32") (pin "1") (pinfunction "1_1") (pintype "passive"))
      (node (ref "C33") (pin "1") (pinfunction "1_1") (pintype "passive"))
      (node (ref "C34") (pin "2") (pinfunction "2_2") (pintype "passive"))
      (node (ref "C35") (pin "2") (pinfunction "2_2") (pintype "passive"))
      (node (ref "C36") (pin "1") (pinfunction "1_1") (pintype "passive"))
      (node (ref "C37") (pin "1") (pinfunction "1_1") (pintype "passive"))
      (node (ref "C38") (pin "1") (pinfunction "1_1") (pintype "passive"))
      (node (ref "C39") (pin "1") (pinfunction "1_1") (pintype "passive"))
      (node (ref "C4") (pin "1") (pinfunction "1_1") (pintype "passive"))
      (node (ref "C40") (pin "1") (pinfunction "1_1") (pintype "passive"))
      (node (ref "C41") (pin "1") (pinfunction "1_1") (pintype "passive"))
      (node (ref "C42") (pin "1") (pinfunction "1_1") (pintype "passive"))
      (node (ref "C43") (pin "1") (pinfunction "1_1") (pintype "passive"))
      (node (ref "C44") (pin "1") (pinfunction "1_1") (pintype "passive"))
      (node (ref "C45") (pin "1") (pinfunction "1_1") (pintype "passive"))
      (node (ref "C46") (pin "1") (pinfunction "1_1") (pintype "passive"))
      (node (ref "C47") (pin "1") (pinfunction "1_1") (pintype "passive"))
      (node (ref "C48") (pin "1") (pinfunction "1_1") (pintype "passive"))
      (node (ref "C49") (pin "1") (pinfunction "1_1") (pintype "passive"))
      (node (ref "C5") (pin "2") (pinfunction "2_2") (pintype "passive"))
      (node (ref "C50") (pin "2") (pinfunction "2_2") (pintype "passive"))
      (node (ref "C6") (pin "2") (pinfunction "2_2") (pintype "passive"))
      (node (ref "C7") (pin "1") (pinfunction "1_1") (pintype "passive"))
      (node (ref "C8") (pin "1") (pinfunction "1_1") (pintype "passive"))
      (node (ref "C9") (pin "1") (pinfunction "1_1") (pintype "passive"))
      (node (ref "D1") (pin "2") (pinfunction "A_2") (pintype "passive"))
      (node (ref "D2") (pin "2") (pinfunction "A_2") (pintype "passive"))
      (node (ref "D3") (pin "2") (pinfunction "A_2") (pintype "passive"))
      (node (ref "D4") (pin "2") (pinfunction "A_2") (pintype "passive"))
      (node (ref "D5") (pin "2") (pinfunction "A_2") (pintype "passive"))
      (node (ref "D6") (pin "2") (pinfunction "A_2") (pintype "passive"))
      (node (ref "D7") (pin "2") (pinfunction "A_2") (pintype "passive"))
      (node (ref "D8") (pin "2") (pinfunction "A_2") (pintype "passive"))
      (node (ref "J1") (pin "2") (pinfunction "V-_2") (pintype "passive"))
      (node (ref "J10") (pin "1") (pinfunction "GND_1") (pintype "passive"))
      (node (ref "J2") (pin "2") (pinfunction "MNT_1_2") (pintype "passive"))
      (node (ref "J3") (pin "2") (pinfunction "MNT_1_2") (pintype "passive"))
      (node (ref "J4") (pin "2") (pinfunction "MNT_1_2") (pintype "passive"))
      (node (ref "J5") (pin "2") (pinfunction "MNT_1_2") (pintype "passive"))
      (node (ref "J6") (pin "2") (pinfunction "MNT_1_2") (pintype "passive"))
      (node (ref "J7") (pin "2") (pinfunction "MNT_1_2") (pintype "passive"))
      (node (ref "J8") (pin "2") (pinfunction "MNT_1_2") (pintype "passive"))
      (node (ref "J9") (pin "2") (pinfunction "MNT_1_2") (pintype "passive"))
      (node (ref "JP1") (pin "1") (pinfunction "1_1") (pintype "passive"))
      (node (ref "JP2") (pin "3") (pinfunction "3_3") (pintype "passive"))
      (node (ref "R12") (pin "2") (pinfunction "2_2") (pintype "passive"))
      (node (ref "R13") (pin "2") (pinfunction "2_2") (pintype "passive"))
      (node (ref "R14") (pin "2") (pinfunction "2_2") (pintype "passive"))
      (node (ref "R15") (pin "2") (pinfunction "2_2") (pintype "passive"))
      (node (ref "R35") (pin "2") (pinfunction "2_2") (pintype "passive"))
      (node (ref "R37") (pin "1") (pinfunction "1_1") (pintype "passive"))
      (node (ref "R4") (pin "1") (pinfunction "1_1") (pintype "passive"))
      (node (ref "R7") (pin "1") (pinfunction "1_1") (pintype "passive"))
      (node (ref "SW2") (pin "2") (pinfunction "2_2") (pintype "passive"))
      (node (ref "U1") (pin "1") (pinfunction "PS/S_1") (pintype "input"))
      (node (ref "U1") (pin "10") (pinfunction "PGND_10") (pintype "power_in"))
      (node (ref "U1") (pin "15") (pinfunction "VSEL_15") (pintype "input"))
      (node (ref "U1") (pin "4") (pinfunction "GND_4") (pintype "power_in"))
      (node (ref "U1") (pin "6") (pinfunction "FB2_6") (pintype "output"))
      (node (ref "U10") (pin "2") (pinfunction "-V_2") (pintype "power_in"))
      (node (ref "U11") (pin "2") (pinfunction "-V_2") (pintype "power_in"))
      (node (ref "U12") (pin "2") (pinfunction "-V_2") (pintype "power_in"))
      (node (ref "U13") (pin "2") (pinfunction "-V_2") (pintype "power_in"))
      (node (ref "U14") (pin "2") (pinfunction "-V_2") (pintype "power_in"))
      (node (ref "U15") (pin "23") (pinfunction "VSS_1_23") (pintype "power_in"))
      (node (ref "U15") (pin "35") (pinfunction "VSS_2_35") (pintype "power_in"))
      (node (ref "U15") (pin "47") (pinfunction "VSS_3_47") (pintype "power_in"))
      (node (ref "U15") (pin "8") (pinfunction "VSSA_8") (pintype "power_in"))
      (node (ref "U2") (pin "4") (pinfunction "GND_4") (pintype "power_in"))
      (node (ref "U2") (pin "9") (pinfunction "GND_9") (pintype "power_in"))
      (node (ref "U3") (pin "1") (pinfunction "ADJ/GND_1") (pintype "power_in"))
      (node (ref "U4") (pin "2") (pinfunction "-V_2") (pintype "power_in"))
      (node (ref "U5") (pin "1") (pinfunction "GND_FORCE_1") (pintype "power_in"))
      (node (ref "U5") (pin "2") (pinfunction "GND_SENSE_2") (pintype "input"))
      (node (ref "U6") (pin "17") (pinfunction "DGND_17") (pintype "power_in"))
      (node (ref "U6") (pin "2") (pinfunction "AGND_2") (pintype "power_in"))
      (node (ref "U6") (pin "3") (pinfunction "VREFN_3") (pintype "input"))
      (node (ref "U6") (pin "5") (pinfunction "AINCOM_5") (pintype "input"))
      (node (ref "U7") (pin "2") (pinfunction "-V_2") (pintype "power_in"))
      (node (ref "U8") (pin "2") (pinfunction "-V_2") (pintype "power_in"))
      (node (ref "U9") (pin "2") (pinfunction "-V_2") (pintype "power_in"))
    )
    (net (code "32") (name "Net-(D1-K)") (class "Default")
      (node (ref "D1") (pin "1") (pinfunction "K_1") (pintype "passive"))
      (node (ref "J2") (pin "1") (pinfunction "1_1") (pintype "passive"))
      (node (ref "U7") (pin "3") (pinfunction "+IN_3") (pintype "input"))
    )
    (net (code "33") (name "Net-(D2-K)") (class "Default")
      (node (ref "D2") (pin "1") (pinfunction "K_1") (pintype "passive"))
      (node (ref "J3") (pin "1") (pinfunction "1_1") (pintype "passive"))
      (node (ref "U8") (pin "3") (pinfunction "+IN_3") (pintype "input"))
    )
    (net (code "34") (name "Net-(D3-K)") (class "Default")
      (node (ref "D3") (pin "1") (pinfunction "K_1") (pintype "passive"))
      (node (ref "J4") (pin "1") (pinfunction "1_1") (pintype "passive"))
      (node (ref "U9") (pin "3") (pinfunction "+IN_3") (pintype "input"))
    )
    (net (code "35") (name "Net-(D4-K)") (class "Default")
      (node (ref "D4") (pin "1") (pinfunction "K_1") (pintype "passive"))
      (node (ref "J5") (pin "1") (pinfunction "1_1") (pintype "passive"))
      (node (ref "U10") (pin "3") (pinfunction "+IN_3") (pintype "input"))
    )
    (net (code "36") (name "Net-(D5-K)") (class "Default")
      (node (ref "D5") (pin "1") (pinfunction "K_1") (pintype "passive"))
      (node (ref "J6") (pin "1") (pinfunction "1_1") (pintype "passive"))
      (node (ref "U11") (pin "3") (pinfunction "+IN_3") (pintype "input"))
    )
    (net (code "37") (name "Net-(D6-K)") (class "Default")
      (node (ref "D6") (pin "1") (pinfunction "K_1") (pintype "passive"))
      (node (ref "J7") (pin "1") (pinfunction "1_1") (pintype "passive"))
      (node (ref "U12") (pin "3") (pinfunction "+IN_3") (pintype "input"))
    )
    (net (code "38") (name "Net-(D7-K)") (class "Default")
      (node (ref "D7") (pin "1") (pinfunction "K_1") (pintype "passive"))
      (node (ref "J8") (pin "1") (pinfunction "1_1") (pintype "passive"))
      (node (ref "U13") (pin "3") (pinfunction "+IN_3") (pintype "input"))
    )
    (net (code "39") (name "Net-(D8-K)") (class "Default")
      (node (ref "D8") (pin "1") (pinfunction "K_1") (pintype "passive"))
      (node (ref "J9") (pin "1") (pinfunction "1_1") (pintype "passive"))
      (node (ref "U14") (pin "3") (pinfunction "+IN_3") (pintype "input"))
    )
    (net (code "40") (name "Net-(U1-EN)") (class "Default")
      (node (ref "R6") (pin "2") (pinfunction "2_2") (pintype "passive"))
      (node (ref "U1") (pin "14") (pinfunction "EN_14") (pintype "input"))
    )
    (net (code "41") (name "Net-(U1-FB)") (class "Default")
      (node (ref "R2") (pin "1") (pinfunction "1_1") (pintype "passive"))
      (node (ref "R4") (pin "2") (pinfunction "2_2") (pintype "passive"))
      (node (ref "U1") (pin "5") (pinfunction "FB_5") (pintype "output"))
    )
    (net (code "42") (name "Net-(U1-PG)") (class "Default")
      (node (ref "R3") (pin "2") (pinfunction "2_2") (pintype "passive"))
      (node (ref "U1") (pin "2") (pinfunction "PG_2") (pintype "open_collector"))
    )
    (net (code "43") (name "Net-(U1-VAUX)") (class "Default")
      (node (ref "C5") (pin "1") (pinfunction "1_1") (pintype "passive"))
      (node (ref "U1") (pin "3") (pinfunction "VAUX_3") (pintype "output"))
    )
    (net (code "44") (name "Net-(U2-FB)") (class "Default")
      (node (ref "R5") (pin "2") (pinfunction "2_2") (pintype "passive"))
      (node (ref "R7") (pin "2") (pinfunction "2_2") (pintype "passive"))
      (node (ref "U2") (pin "3") (pinfunction "FB_3") (pintype "input"))
    )
    (net (code "45") (name "Net-(U2-NR)") (class "Default")
      (node (ref "C9") (pin "2") (pinfunction "2_2") (pintype "passive"))
      (node (ref "U2") (pin "6") (pinfunction "NR_6") (pintype "passive"))
    )
    (net (code "46") (name "Net-(U4-+IN)") (class "Default")
      (node (ref "C12") (pin "2") (pinfunction "2_2") (pintype "passive"))
      (node (ref "U4") (pin "3") (pinfunction "+IN_3") (pintype "input"))
      (node (ref "U5") (pin "5") (pinfunction "VOUT_SENSE_5") (pintype "input"))
      (node (ref "U5") (pin "6") (pinfunction "VOUT_FORCE_6") (pintype "power_in"))
    )
    (net (code "47") (name "Net-(U4--IN)") (class "Default")
      (node (ref "R1") (pin "1") (pinfunction "1_1") (pintype "passive"))
      (node (ref "U4") (pin "4") (pinfunction "-IN_4") (pintype "input"))
    )
    (net (code "48") (name "Net-(U6-D0{slash}CLKOUT)") (class "Default")
      (node (ref "R12") (pin "1") (pinfunction "1_1") (pintype "passive"))
      (node (ref "U6") (pin "25") (pinfunction "D0/CLKOUT_25") (pintype "bidirectional"))
    )
    (net (code "49") (name "Net-(U6-D1)") (class "Default")
      (node (ref "R13") (pin "1") (pinfunction "1_1") (pintype "passive"))
      (node (ref "U6") (pin "26") (pinfunction "D1_26") (pintype "bidirectional"))
    )
    (net (code "50") (name "Net-(U6-D2)") (class "Default")
      (node (ref "R14") (pin "1") (pinfunction "1_1") (pintype "passive"))
      (node (ref "U6") (pin "27") (pinfunction "D2_27") (pintype "bidirectional"))
    )
    (net (code "51") (name "Net-(U6-D3)") (class "Default")
      (node (ref "R15") (pin "1") (pinfunction "1_1") (pintype "passive"))
      (node (ref "U6") (pin "28") (pinfunction "D3_28") (pintype "bidirectional"))
    )
    (net (code "52") (name "Net-(U7--IN)") (class "Default")
      (node (ref "R8") (pin "1") (pinfunction "1_1") (pintype "passive"))
      (node (ref "U7") (pin "4") (pinfunction "-IN_4") (pintype "input"))
    )
    (net (code "53") (name "Net-(U7-OUT)") (class "Default")
      (node (ref "R16") (pin "1") (pinfunction "1_1") (pintype "passive"))
      (node (ref "R8") (pin "2") (pinfunction "2_2") (pintype "passive"))
      (node (ref "U7") (pin "1") (pinfunction "OUT_1") (pintype "output"))
    )
    (net (code "54") (name "Net-(U8--IN)") (class "Default")
      (node (ref "R9") (pin "1") (pinfunction "1_1") (pintype "passive"))
      (node (ref "U8") (pin "4") (pinfunction "-IN_4") (pintype "input"))
    )
    (net (code "55") (name "Net-(U8-OUT)") (class "Default")
      (node (ref "R17") (pin "1") (pinfunction "1_1") (pintype "passive"))
      (node (ref "R9") (pin "2") (pinfunction "2_2") (pintype "passive"))
      (node (ref "U8") (pin "1") (pinfunction "OUT_1") (pintype "output"))
    )
    (net (code "56") (name "Net-(U9--IN)") (class "Default")
      (node (ref "R10") (pin "1") (pinfunction "1_1") (pintype "passive"))
      (node (ref "U9") (pin "4") (pinfunction "-IN_4") (pintype "input"))
    )
    (net (code "57") (name "Net-(U9-OUT)") (class "Default")
      (node (ref "R10") (pin "2") (pinfunction "2_2") (pintype "passive"))
      (node (ref "R18") (pin "1") (pinfunction "1_1") (pintype "passive"))
      (node (ref "U9") (pin "1") (pinfunction "OUT_1") (pintype "output"))
    )
    (net (code "58") (name "Net-(U10--IN)") (class "Default")
      (node (ref "R11") (pin "1") (pinfunction "1_1") (pintype "passive"))
      (node (ref "U10") (pin "4") (pinfunction "-IN_4") (pintype "input"))
    )
    (net (code "59") (name "Net-(U10-OUT)") (class "Default")
      (node (ref "R11") (pin "2") (pinfunction "2_2") (pintype "passive"))
      (node (ref "R19") (pin "1") (pinfunction "1_1") (pintype "passive"))
      (node (ref "U10") (pin "1") (pinfunction "OUT_1") (pintype "output"))
    )
    (net (code "60") (name "Net-(U11--IN)") (class "Default")
      (node (ref "R20") (pin "1") (pinfunction "1_1") (pintype "passive"))
      (node (ref "U11") (pin "4") (pinfunction "-IN_4") (pintype "input"))
    )
    (net (code "61") (name "Net-(U11-OUT)") (class "Default")
      (node (ref "R20") (pin "2") (pinfunction "2_2") (pintype "passive"))
      (node (ref "R24") (pin "1") (pinfunction "1_1") (pintype "passive"))
      (node (ref "U11") (pin "1") (pinfunction "OUT_1") (pintype "output"))
    )
    (net (code "62") (name "Net-(U12--IN)") (class "Default")
      (node (ref "R21") (pin "1") (pinfunction "1_1") (pintype "passive"))
      (node (ref "U12") (pin "4") (pinfunction "-IN_4") (pintype "input"))
    )
    (net (code "63") (name "Net-(U12-OUT)") (class "Default")
      (node (ref "R21") (pin "2") (pinfunction "2_2") (pintype "passive"))
      (node (ref "R25") (pin "1") (pinfunction "1_1") (pintype "passive"))
      (node (ref "U12") (pin "1") (pinfunction "OUT_1") (pintype "output"))
    )
    (net (code "64") (name "Net-(U13--IN)") (class "Default")
      (node (ref "R22") (pin "1") (pinfunction "1_1") (pintype "passive"))
      (node (ref "U13") (pin "4") (pinfunction "-IN_4") (pintype "input"))
    )
    (net (code "65") (name "Net-(U13-OUT)") (class "Default")
      (node (ref "R22") (pin "2") (pinfunction "2_2") (pintype "passive"))
      (node (ref "R26") (pin "1") (pinfunction "1_1") (pintype "passive"))
      (node (ref "U13") (pin "1") (pinfunction "OUT_1") (pintype "output"))
    )
    (net (code "66") (name "Net-(U14--IN)") (class "Default")
      (node (ref "R23") (pin "1") (pinfunction "1_1") (pintype "passive"))
      (node (ref "U14") (pin "4") (pinfunction "-IN_4") (pintype "input"))
    )
    (net (code "67") (name "Net-(U14-OUT)") (class "Default")
      (node (ref "R23") (pin "2") (pinfunction "2_2") (pintype "passive"))
      (node (ref "R27") (pin "1") (pinfunction "1_1") (pintype "passive"))
      (node (ref "U14") (pin "1") (pinfunction "OUT_1") (pintype "output"))
    )
    (net (code "68") (name "Net-(U15A-BOOT0)") (class "Default")
      (node (ref "R36") (pin "1") (pinfunction "1_1") (pintype "passive"))
      (node (ref "U15") (pin "44") (pinfunction "BOOT0_44") (pintype "input"))
    )
    (net (code "69") (name "Net-(U15A-PB2)") (class "Default")
      (node (ref "R29") (pin "1") (pinfunction "1_1") (pintype "passive"))
      (node (ref "U15") (pin "20") (pinfunction "PB2_20") (pintype "bidirectional"))
    )
    (net (code "70") (name "Net-(U15A-PB5)") (class "Default")
      (node (ref "R30") (pin "1") (pinfunction "1_1") (pintype "passive"))
      (node (ref "U15") (pin "41") (pinfunction "PB5_41") (pintype "bidirectional"))
    )
    (net (code "71") (name "Net-(U15A-PB6)") (class "Default")
      (node (ref "R31") (pin "1") (pinfunction "1_1") (pintype "passive"))
      (node (ref "U15") (pin "42") (pinfunction "PB6_42") (pintype "bidirectional"))
    )
    (net (code "72") (name "Net-(U15A-PB7)") (class "Default")
      (node (ref "R32") (pin "1") (pinfunction "1_1") (pintype "passive"))
      (node (ref "U15") (pin "43") (pinfunction "PB7_43") (pintype "bidirectional"))
    )
    (net (code "73") (name "Net-(U15A-PB8)") (class "Default")
      (node (ref "R33") (pin "1") (pinfunction "1_1") (pintype "passive"))
      (node (ref "U15") (pin "45") (pinfunction "PB8_45") (pintype "bidirectional"))
    )
    (net (code "74") (name "Net-(U15A-PB9)") (class "Default")
      (node (ref "R34") (pin "1") (pinfunction "1_1") (pintype "passive"))
      (node (ref "U15") (pin "46") (pinfunction "PB9_46") (pintype "bidirectional"))
    )
    (net (code "75") (name "VIN") (class "Default")
      (node (ref "C14") (pin "1") (pinfunction "1_1") (pintype "passive"))
      (node (ref "C3") (pin "2") (pinfunction "2_2") (pintype "passive"))
      (node (ref "C4") (pin "2") (pinfunction "2_2") (pintype "passive"))
      (node (ref "J1") (pin "1") (pinfunction "V+_1") (pintype "passive"))
      (node (ref "JP1") (pin "2") (pinfunction "2_2") (pintype "passive"))
      (node (ref "R6") (pin "1") (pinfunction "1_1") (pintype "passive"))
      (node (ref "U1") (pin "12-13") (pinfunction "VIN_12-13") (pintype "power_in"))
    )
    (net (code "76") (name "unconnected-(J10-VCC-Pad4)") (class "Default")
      (node (ref "J10") (pin "4") (pinfunction "VCC_4") (pintype "passive+no_connect"))
    )
    (net (code "77") (name "unconnected-(U15A-PA0-WKUP-Pad10)") (class "Default")
      (node (ref "U15") (pin "10") (pinfunction "PA0-WKUP_10") (pintype "bidirectional+no_connect"))
    )
    (net (code "78") (name "unconnected-(U15A-PA1-Pad11)") (class "Default")
      (node (ref "U15") (pin "11") (pinfunction "PA1_11") (pintype "bidirectional+no_connect"))
    )
    (net (code "79") (name "unconnected-(U15A-PA2-Pad12)") (class "Default")
      (node (ref "U15") (pin "12") (pinfunction "PA2_12") (pintype "bidirectional+no_connect"))
    )
    (net (code "80") (name "unconnected-(U15A-PA3-Pad13)") (class "Default")
      (node (ref "U15") (pin "13") (pinfunction "PA3_13") (pintype "bidirectional+no_connect"))
    )
    (net (code "81") (name "unconnected-(U15A-PA4-Pad14)") (class "Default")
      (node (ref "U15") (pin "14") (pinfunction "PA4_14") (pintype "bidirectional+no_connect"))
    )
    (net (code "82") (name "unconnected-(U15A-PA5-Pad15)") (class "Default")
      (node (ref "U15") (pin "15") (pinfunction "PA5_15") (pintype "bidirectional+no_connect"))
    )
    (net (code "83") (name "unconnected-(U15A-PA6-Pad16)") (class "Default")
      (node (ref "U15") (pin "16") (pinfunction "PA6_16") (pintype "bidirectional+no_connect"))
    )
    (net (code "84") (name "unconnected-(U15A-PA7-Pad17)") (class "Default")
      (node (ref "U15") (pin "17") (pinfunction "PA7_17") (pintype "bidirectional+no_connect"))
    )
    (net (code "85") (name "unconnected-(U15A-PA8-Pad29)") (class "Default")
      (node (ref "U15") (pin "29") (pinfunction "PA8_29") (pintype "bidirectional+no_connect"))
    )
    (net (code "86") (name "unconnected-(U15A-PA11-Pad32)") (class "Default")
      (node (ref "U15") (pin "32") (pinfunction "PA11_32") (pintype "bidirectional+no_connect"))
    )
    (net (code "87") (name "unconnected-(U15A-PA12-Pad33)") (class "Default")
      (node (ref "U15") (pin "33") (pinfunction "PA12_33") (pintype "bidirectional+no_connect"))
    )
    (net (code "88") (name "unconnected-(U15A-PA15-Pad38)") (class "Default")
      (node (ref "U15") (pin "38") (pinfunction "PA15_38") (pintype "bidirectional+no_connect"))
    )
    (net (code "89") (name "unconnected-(U15A-PB0-Pad18)") (class "Default")
      (node (ref "U15") (pin "18") (pinfunction "PB0_18") (pintype "bidirectional+no_connect"))
    )
    (net (code "90") (name "unconnected-(U15A-PB1-Pad19)") (class "Default")
      (node (ref "U15") (pin "19") (pinfunction "PB1_19") (pintype "bidirectional+no_connect"))
    )
    (net (code "91") (name "unconnected-(U15A-PB3-Pad39)") (class "Default")
      (node (ref "U15") (pin "39") (pinfunction "PB3_39") (pintype "bidirectional+no_connect"))
    )
    (net (code "92") (name "unconnected-(U15A-PB4-Pad40)") (class "Default")
      (node (ref "U15") (pin "40") (pinfunction "PB4_40") (pintype "bidirectional+no_connect"))
    )
    (net (code "93") (name "unconnected-(U15A-PB10-Pad21)") (class "Default")
      (node (ref "U15") (pin "21") (pinfunction "PB10_21") (pintype "bidirectional+no_connect"))
    )
    (net (code "94") (name "unconnected-(U15A-PB11-Pad22)") (class "Default")
      (node (ref "U15") (pin "22") (pinfunction "PB11_22") (pintype "bidirectional+no_connect"))
    )
    (net (code "95") (name "unconnected-(U15A-PB12-Pad25)") (class "Default")
      (node (ref "U15") (pin "25") (pinfunction "PB12_25") (pintype "bidirectional+no_connect"))
    )
    (net (code "96") (name "unconnected-(U15A-PB13-Pad26)") (class "Default")
      (node (ref "U15") (pin "26") (pinfunction "PB13_26") (pintype "bidirectional+no_connect"))
    )
    (net (code "97") (name "unconnected-(U15A-PB14-Pad27)") (class "Default")
      (node (ref "U15") (pin "27") (pinfunction "PB14_27") (pintype "bidirectional+no_connect"))
    )
    (net (code "98") (name "unconnected-(U15A-PB15-Pad28)") (class "Default")
      (node (ref "U15") (pin "28") (pinfunction "PB15_28") (pintype "bidirectional+no_connect"))
    )
    (net (code "99") (name "unconnected-(U15A-PC13-TAMPER-RTC-Pad2)") (class "Default")
      (node (ref "U15") (pin "2") (pinfunction "PC13-TAMPER-RTC_2") (pintype "bidirectional+no_connect"))
    )
    (net (code "100") (name "unconnected-(U15A-PC14-OSC32_IN-Pad3)") (class "Default")
      (node (ref "U15") (pin "3") (pinfunction "PC14-OSC32_IN_3") (pintype "bidirectional+no_connect"))
    )
    (net (code "101") (name "unconnected-(U15A-PC15-OSC32_OUT-Pad4)") (class "Default")
      (node (ref "U15") (pin "4") (pinfunction "PC15-OSC32_OUT_4") (pintype "bidirectional+no_connect"))
    )
  )
)
